# 01-PCIe_40pin.net
KiCad netlist of a schematic drawn in Altium Designer
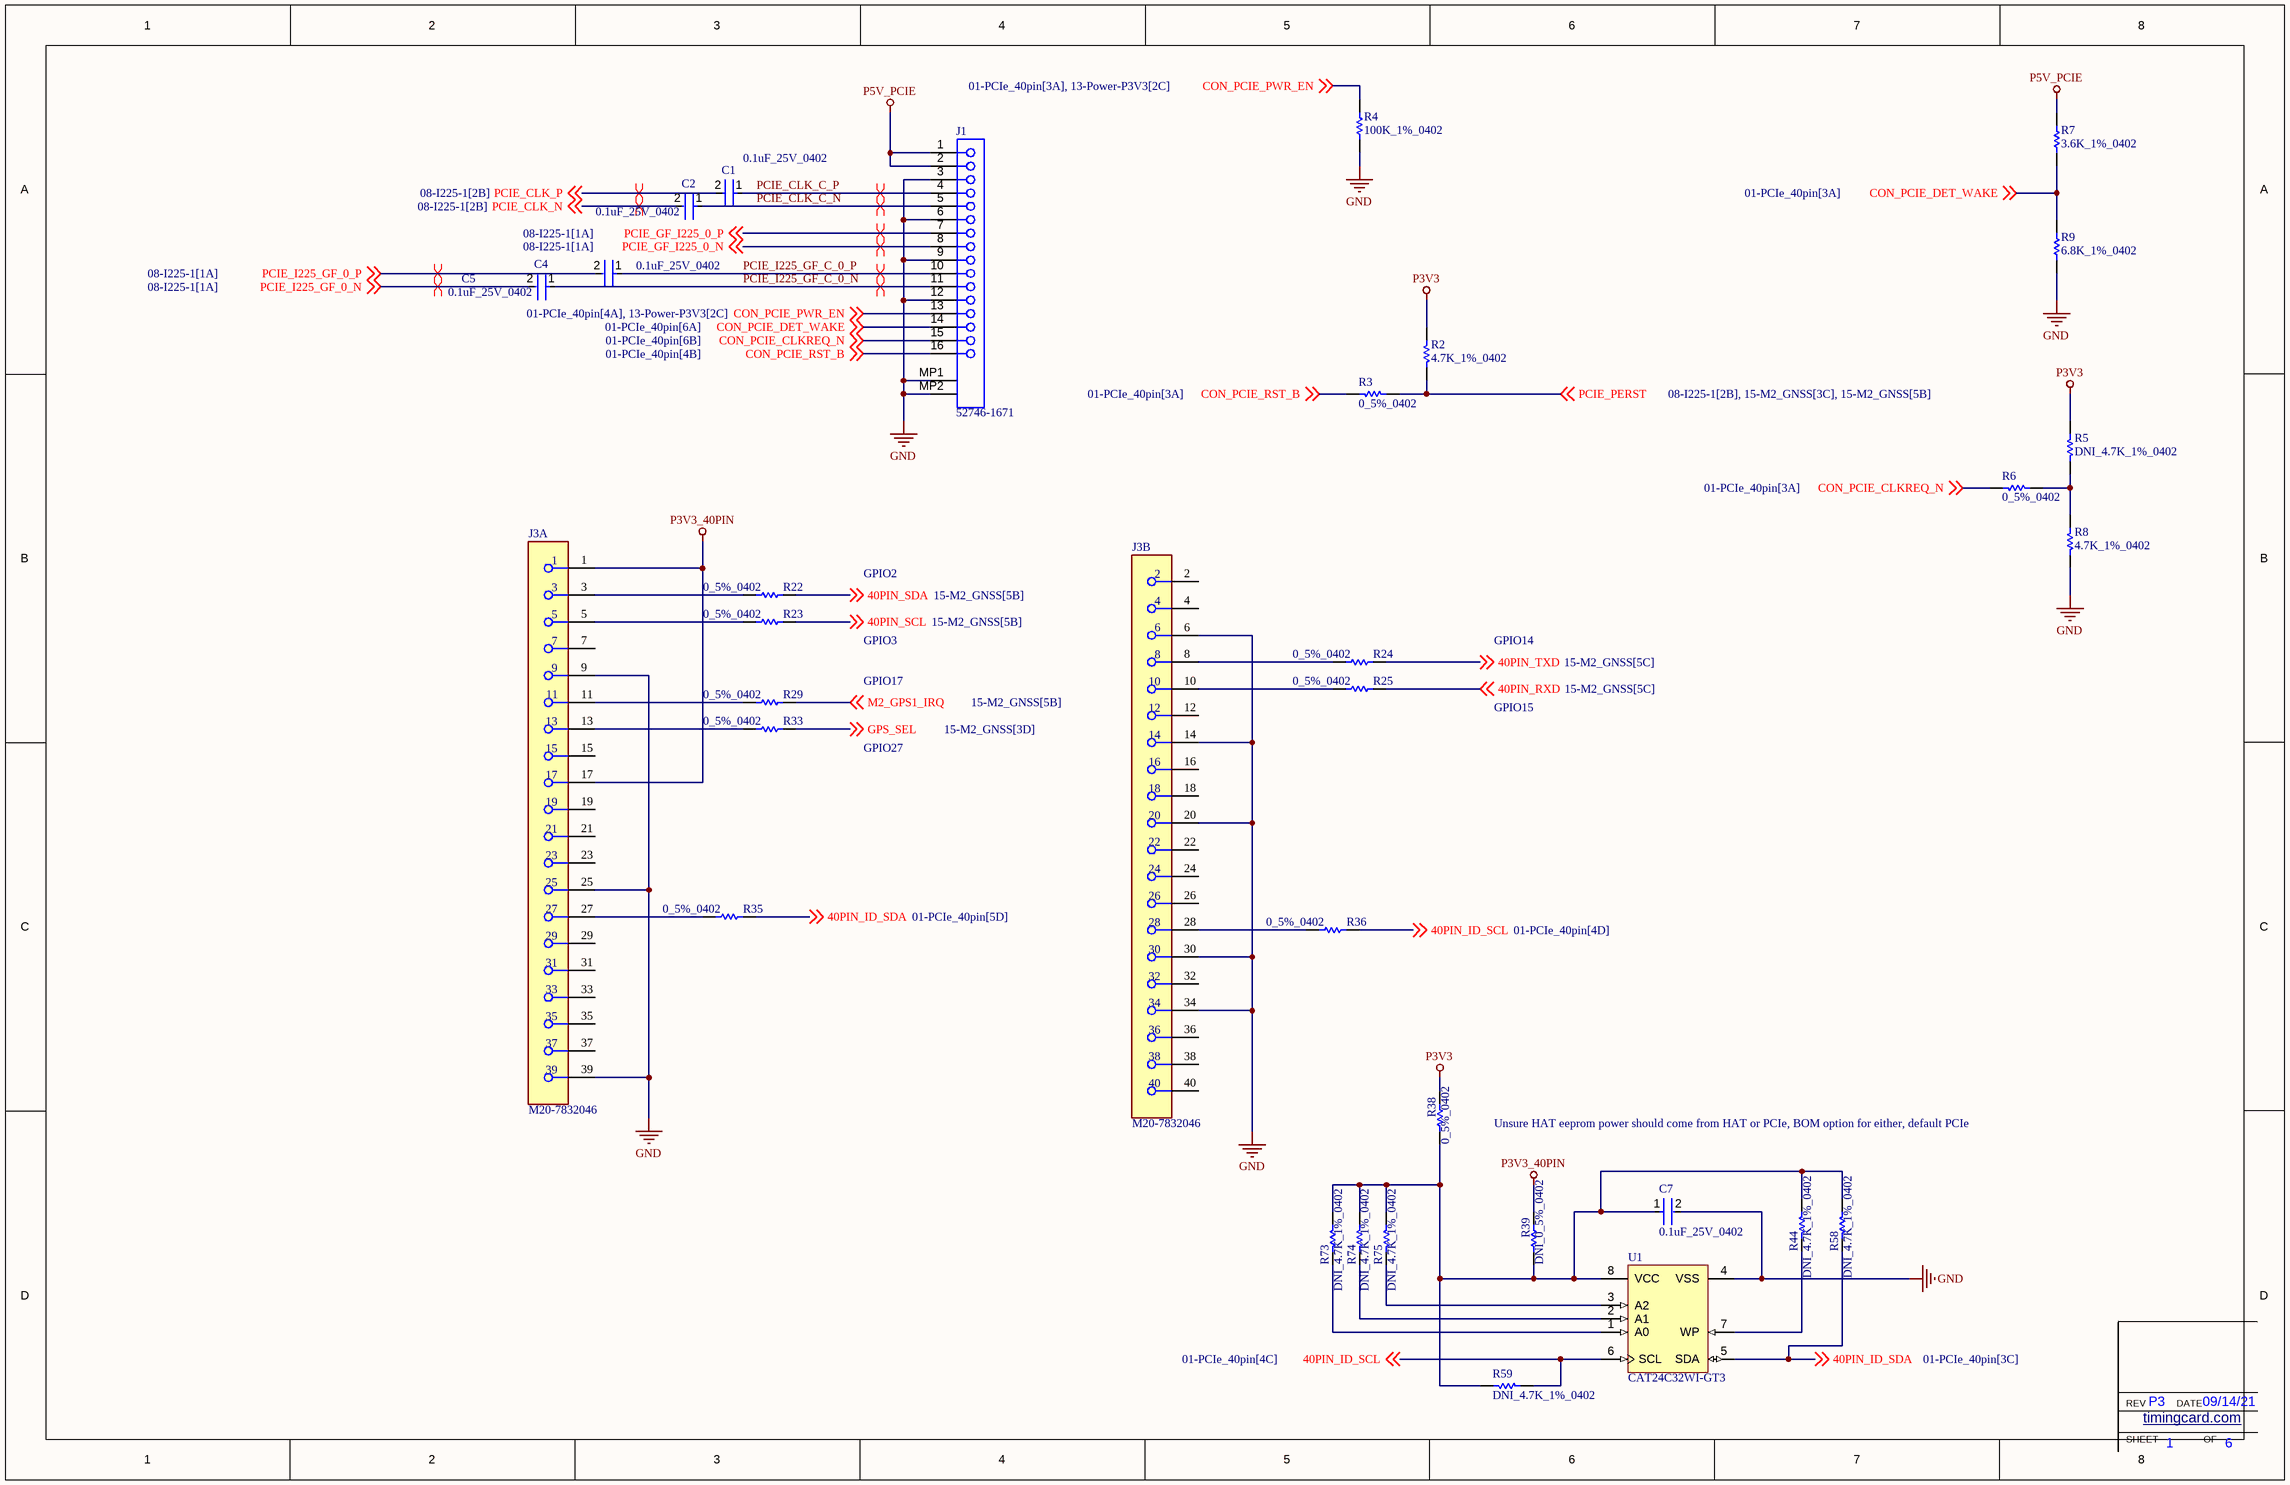
[diagram p0: 01-PCIe_40pin.SchDoc]

(export (version "E")
  (design (tool "Eeschema 10.0.6"))
  (components
    (comp (ref "C1")
      (value "0.1uF_25V_0402")
      (footprint "FP-0402-L_1_0_1-W_0_5_0_1-IPC_C")
      (description "General Purpose Ceramic Capacitor, 0402, 100nF, 10%, X7R, 15%, 25V")
      (fields (field (name "VOLTAGE") "25V") (field (name "TOLERANCE") "10%"))
      (libsource (lib "Altium Content Vault") (part "b4654b650e69147ec39a6b967a45e02"))
    )
    (comp (ref "C2")
      (value "0.1uF_25V_0402")
      (footprint "FP-0402-L_1_0_1-W_0_5_0_1-IPC_C")
      (description "General Purpose Ceramic Capacitor, 0402, 100nF, 10%, X7R, 15%, 25V")
      (fields (field (name "VOLTAGE") "25V") (field (name "TOLERANCE") "10%"))
      (libsource (lib "Altium Content Vault") (part "b4654b650e69147ec39a6b967a45e02"))
    )
    (comp (ref "C4")
      (value "0.1uF_25V_0402")
      (footprint "FP-0402-L_1_0_1-W_0_5_0_1-IPC_C")
      (description "General Purpose Ceramic Capacitor, 0402, 100nF, 10%, X7R, 15%, 25V")
      (fields (field (name "VOLTAGE") "25V") (field (name "TOLERANCE") "10%"))
      (libsource (lib "Altium Content Vault") (part "b4654b650e69147ec39a6b967a45e02"))
    )
    (comp (ref "C5")
      (value "0.1uF_25V_0402")
      (footprint "FP-0402-L_1_0_1-W_0_5_0_1-IPC_C")
      (description "General Purpose Ceramic Capacitor, 0402, 100nF, 10%, X7R, 15%, 25V")
      (fields (field (name "VOLTAGE") "25V") (field (name "TOLERANCE") "10%"))
      (libsource (lib "Altium Content Vault") (part "b4654b650e69147ec39a6b967a45e02"))
    )
    (comp (ref "C7")
      (value "0.1uF_25V_0402")
      (footprint "FP-0402-L_1_0_1-W_0_5_0_1-IPC_C")
      (description "General Purpose Ceramic Capacitor, 0402, 100nF, 10%, X7R, 15%, 25V")
      (fields (field (name "VOLTAGE") "25V") (field (name "TOLERANCE") "10%"))
      (libsource (lib "Altium Content Vault") (part "b4654b650e69147ec39a6b967a45e02"))
    )
    (comp (ref "J1")
      (value "52746-1671")
      (footprint "MOLX-52746-1671")
      (fields (field (name "MANUFACTURER") "Molex"))
      (libsource (lib "Altium Content Vault") (part "MOLX-52746-1671"))
    )
    (comp (ref "J3")
      (value "M20-7832046")
      (footprint "FP-M20-7832046-MFG")
      (description "CONN RCPT 40POS 0.1 TIN PCB")
      (libsource (lib "Altium Content Vault") (part "e49c40d8a4b72700ef4f9e86232dadc"))
    )
    (comp (ref "R2")
      (value "4.7K_1%_0402")
      (footprint "RESC1005X40X25NL10T10")
      (fields (field (name "MANUFACTURER") "Bourns") (field (name "PART NUMBER") "CR0402-FX-4701GLF"))
      (libsource (lib "Altium Content Vault") (part "RES"))
    )
    (comp (ref "R3")
      (value "0_5%_0402")
      (footprint "RESC1005X40X25LL10T10")
      (fields (field (name "MANUFACTURER") "KOA Speer") (field (name "PART NUMBER") "RK73Z1ETTP"))
      (libsource (lib "Altium Content Vault") (part "RES"))
    )
    (comp (ref "R4")
      (value "100K_1%_0402")
      (footprint "RESC1005X40X25ML05T10")
      (fields (field (name "MANUFACTURER") "Yageo") (field (name "PART NUMBER") "RC0402FR-13100KL"))
      (libsource (lib "Altium Content Vault") (part "RES"))
    )
    (comp (ref "R5")
      (value "DNI_4.7K_1%_0402")
      (footprint "RESC1005X40X25NL10T10")
      (fields (field (name "MANUFACTURER") "Bourns") (field (name "PART NUMBER") "CR0402-FX-4701GLF"))
      (libsource (lib "Altium Content Vault") (part "RES"))
    )
    (comp (ref "R6")
      (value "0_5%_0402")
      (footprint "RESC1005X40X25LL10T10")
      (fields (field (name "MANUFACTURER") "KOA Speer") (field (name "PART NUMBER") "RK73Z1ETTP"))
      (libsource (lib "Altium Content Vault") (part "RES"))
    )
    (comp (ref "R7")
      (value "3.6K_1%_0402")
      (footprint "RESC1005X40X25ML05T10")
      (fields (field (name "MANUFACTURER") "Yageo / Phycomp") (field (name "PART NUMBER") "RC0402FR-073K6L"))
      (libsource (lib "Altium Content Vault") (part "RES"))
    )
    (comp (ref "R8")
      (value "4.7K_1%_0402")
      (footprint "RESC1005X40X25NL10T10")
      (fields (field (name "MANUFACTURER") "Bourns") (field (name "PART NUMBER") "CR0402-FX-4701GLF"))
      (libsource (lib "Altium Content Vault") (part "RES"))
    )
    (comp (ref "R9")
      (value "6.8K_1%_0402")
      (footprint "RESC1005X40X25LL10T10")
      (fields (field (name "PART NUMBER") "MC00625W040216K8") (field (name "MANUFACTURER") "Multicomp"))
      (libsource (lib "Altium Content Vault") (part "RES"))
    )
    (comp (ref "R22")
      (value "0_5%_0402")
      (footprint "RESC1005X40X25LL10T10")
      (fields (field (name "MANUFACTURER") "KOA Speer") (field (name "PART NUMBER") "RK73Z1ETTP"))
      (libsource (lib "Altium Content Vault") (part "RES"))
    )
    (comp (ref "R23")
      (value "0_5%_0402")
      (footprint "RESC1005X40X25LL10T10")
      (fields (field (name "MANUFACTURER") "KOA Speer") (field (name "PART NUMBER") "RK73Z1ETTP"))
      (libsource (lib "Altium Content Vault") (part "RES"))
    )
    (comp (ref "R24")
      (value "0_5%_0402")
      (footprint "RESC1005X40X25LL10T10")
      (fields (field (name "MANUFACTURER") "KOA Speer") (field (name "PART NUMBER") "RK73Z1ETTP"))
      (libsource (lib "Altium Content Vault") (part "RES"))
    )
    (comp (ref "R25")
      (value "0_5%_0402")
      (footprint "RESC1005X40X25LL10T10")
      (fields (field (name "MANUFACTURER") "KOA Speer") (field (name "PART NUMBER") "RK73Z1ETTP"))
      (libsource (lib "Altium Content Vault") (part "RES"))
    )
    (comp (ref "R29")
      (value "0_5%_0402")
      (footprint "RESC1005X40X25LL10T10")
      (fields (field (name "MANUFACTURER") "KOA Speer") (field (name "PART NUMBER") "RK73Z1ETTP"))
      (libsource (lib "Altium Content Vault") (part "RES"))
    )
    (comp (ref "R33")
      (value "0_5%_0402")
      (footprint "RESC1005X40X25LL10T10")
      (fields (field (name "MANUFACTURER") "KOA Speer") (field (name "PART NUMBER") "RK73Z1ETTP"))
      (libsource (lib "Altium Content Vault") (part "RES"))
    )
    (comp (ref "R35")
      (value "0_5%_0402")
      (footprint "RESC1005X40X25LL10T10")
      (fields (field (name "MANUFACTURER") "KOA Speer") (field (name "PART NUMBER") "RK73Z1ETTP"))
      (libsource (lib "Altium Content Vault") (part "RES"))
    )
    (comp (ref "R36")
      (value "0_5%_0402")
      (footprint "RESC1005X40X25LL10T10")
      (fields (field (name "MANUFACTURER") "KOA Speer") (field (name "PART NUMBER") "RK73Z1ETTP"))
      (libsource (lib "Altium Content Vault") (part "RES"))
    )
    (comp (ref "R38")
      (value "0_5%_0402")
      (footprint "RESC1005X40X25LL10T10")
      (fields (field (name "MANUFACTURER") "KOA Speer") (field (name "PART NUMBER") "RK73Z1ETTP"))
      (libsource (lib "Altium Content Vault") (part "RES"))
    )
    (comp (ref "R39")
      (value "DNI_0_5%_0402")
      (footprint "RESC1005X40X25LL10T10")
      (fields (field (name "MANUFACTURER") "KOA Speer") (field (name "PART NUMBER") "RK73Z1ETTP"))
      (libsource (lib "Altium Content Vault") (part "RES"))
    )
    (comp (ref "R44")
      (value "DNI_4.7K_1%_0402")
      (footprint "RESC1005X40X25NL10T10")
      (fields (field (name "MANUFACTURER") "Bourns") (field (name "PART NUMBER") "CR0402-FX-4701GLF"))
      (libsource (lib "Altium Content Vault") (part "RES"))
    )
    (comp (ref "R58")
      (value "DNI_4.7K_1%_0402")
      (footprint "RESC1005X40X25NL10T10")
      (fields (field (name "MANUFACTURER") "Bourns") (field (name "PART NUMBER") "CR0402-FX-4701GLF"))
      (libsource (lib "Altium Content Vault") (part "RES"))
    )
    (comp (ref "R59")
      (value "DNI_4.7K_1%_0402")
      (footprint "RESC1005X40X25NL10T10")
      (fields (field (name "MANUFACTURER") "Bourns") (field (name "PART NUMBER") "CR0402-FX-4701GLF"))
      (libsource (lib "Altium Content Vault") (part "RES"))
    )
    (comp (ref "R73")
      (value "DNI_4.7K_1%_0402")
      (footprint "RESC1005X40X25NL10T10")
      (fields (field (name "MANUFACTURER") "Bourns") (field (name "PART NUMBER") "CR0402-FX-4701GLF"))
      (libsource (lib "Altium Content Vault") (part "RES"))
    )
    (comp (ref "R74")
      (value "DNI_4.7K_1%_0402")
      (footprint "RESC1005X40X25NL10T10")
      (fields (field (name "MANUFACTURER") "Bourns") (field (name "PART NUMBER") "CR0402-FX-4701GLF"))
      (libsource (lib "Altium Content Vault") (part "RES"))
    )
    (comp (ref "R75")
      (value "DNI_4.7K_1%_0402")
      (footprint "RESC1005X40X25NL10T10")
      (fields (field (name "MANUFACTURER") "Bourns") (field (name "PART NUMBER") "CR0402-FX-4701GLF"))
      (libsource (lib "Altium Content Vault") (part "RES"))
    )
    (comp (ref "U1")
      (value "CAT24C32WI-GT3")
      (footprint "ONSC-SOIC-8-751BD-01_M")
      (libsource (lib "Altium Content Vault") (part "ONSC-CAT24C32-SOIC-8"))
    )
  )
  (nets
    (net (code "1") (name "/PCIE_CLK_C_N") (class "Default")
      (node (ref "C2") (pin "1") (pinfunction "1_1") (pintype "passive"))
      (node (ref "J1") (pin "5") (pinfunction "5_5") (pintype "passive"))
    )
    (net (code "2") (name "/PCIE_CLK_C_P") (class "Default")
      (node (ref "C1") (pin "1") (pinfunction "1_1") (pintype "passive"))
      (node (ref "J1") (pin "4") (pinfunction "4_4") (pintype "passive"))
    )
    (net (code "3") (name "/PCIE_I225_GF_C_0_N") (class "Default")
      (node (ref "C4") (pin "1") (pinfunction "1_1") (pintype "passive"))
      (node (ref "J1") (pin "11") (pinfunction "11_11") (pintype "passive"))
    )
    (net (code "4") (name "/PCIE_I225_GF_C_0_P") (class "Default")
      (node (ref "C5") (pin "1") (pinfunction "1_1") (pintype "passive"))
      (node (ref "J1") (pin "10") (pinfunction "10_10") (pintype "passive"))
    )
    (net (code "5") (name "40PIN_ID_SCL") (class "Default")
      (node (ref "R36") (pin "2") (pinfunction "2_2") (pintype "passive"))
      (node (ref "R59") (pin "1") (pinfunction "1_1") (pintype "passive"))
      (node (ref "U1") (pin "6") (pinfunction "SCL_6") (pintype "input"))
    )
    (net (code "6") (name "40PIN_ID_SDA") (class "Default")
      (node (ref "R35") (pin "2") (pinfunction "2_2") (pintype "passive"))
      (node (ref "R58") (pin "1") (pinfunction "1_1") (pintype "passive"))
      (node (ref "U1") (pin "5") (pinfunction "SDA_5") (pintype "bidirectional"))
    )
    (net (code "7") (name "40PIN_RXD") (class "Default")
      (node (ref "R25") (pin "2") (pinfunction "2_2") (pintype "passive"))
    )
    (net (code "8") (name "40PIN_SCL") (class "Default")
      (node (ref "R23") (pin "2") (pinfunction "2_2") (pintype "passive"))
    )
    (net (code "9") (name "40PIN_SDA") (class "Default")
      (node (ref "R22") (pin "2") (pinfunction "2_2") (pintype "passive"))
    )
    (net (code "10") (name "40PIN_TXD") (class "Default")
      (node (ref "R24") (pin "2") (pinfunction "2_2") (pintype "passive"))
    )
    (net (code "11") (name "CON_PCIE_CLKREQ_N") (class "Default")
      (node (ref "J1") (pin "15") (pinfunction "15_15") (pintype "passive"))
      (node (ref "R6") (pin "2") (pinfunction "2_2") (pintype "passive"))
    )
    (net (code "12") (name "CON_PCIE_DET_WAKE") (class "Default")
      (node (ref "J1") (pin "14") (pinfunction "14_14") (pintype "passive"))
      (node (ref "R7") (pin "1") (pinfunction "1_1") (pintype "passive"))
      (node (ref "R9") (pin "2") (pinfunction "2_2") (pintype "passive"))
    )
    (net (code "13") (name "CON_PCIE_PWR_EN") (class "Default")
      (node (ref "J1") (pin "13") (pinfunction "13_13") (pintype "passive"))
      (node (ref "R4") (pin "2") (pinfunction "2_2") (pintype "passive"))
    )
    (net (code "14") (name "CON_PCIE_RST_B") (class "Default")
      (node (ref "J1") (pin "16") (pinfunction "16_16") (pintype "passive"))
      (node (ref "R3") (pin "2") (pinfunction "2_2") (pintype "passive"))
    )
    (net (code "15") (name "GND") (class "Default")
      (node (ref "C7") (pin "2") (pinfunction "2_2") (pintype "passive"))
      (node (ref "J1") (pin "12") (pinfunction "12_12") (pintype "passive"))
      (node (ref "J1") (pin "3") (pinfunction "3_3") (pintype "passive"))
      (node (ref "J1") (pin "6") (pinfunction "6_6") (pintype "passive"))
      (node (ref "J1") (pin "9") (pinfunction "9_9") (pintype "passive"))
      (node (ref "J1") (pin "MP1") (pinfunction "MP1_MP1") (pintype "passive"))
      (node (ref "J1") (pin "MP2") (pinfunction "MP2_MP2") (pintype "passive"))
      (node (ref "J3") (pin "14") (pinfunction "14_14") (pintype "passive"))
      (node (ref "J3") (pin "20") (pinfunction "20_20") (pintype "passive"))
      (node (ref "J3") (pin "25") (pinfunction "25_25") (pintype "passive"))
      (node (ref "J3") (pin "30") (pinfunction "30_30") (pintype "passive"))
      (node (ref "J3") (pin "34") (pinfunction "34_34") (pintype "passive"))
      (node (ref "J3") (pin "39") (pinfunction "39_39") (pintype "passive"))
      (node (ref "J3") (pin "6") (pinfunction "6_6") (pintype "passive"))
      (node (ref "J3") (pin "9") (pinfunction "9_9") (pintype "passive"))
      (node (ref "R4") (pin "1") (pinfunction "1_1") (pintype "passive"))
      (node (ref "R8") (pin "1") (pinfunction "1_1") (pintype "passive"))
      (node (ref "R9") (pin "1") (pinfunction "1_1") (pintype "passive"))
      (node (ref "U1") (pin "4") (pinfunction "VSS_4") (pintype "power_in"))
    )
    (net (code "16") (name "GPS_SEL") (class "Default")
      (node (ref "R33") (pin "2") (pinfunction "2_2") (pintype "passive"))
    )
    (net (code "17") (name "M2_GPS1_IRQ") (class "Default")
      (node (ref "R29") (pin "2") (pinfunction "2_2") (pintype "passive"))
    )
    (net (code "18") (name "Net-(J3-Pad3)") (class "Default")
      (node (ref "J3") (pin "3") (pinfunction "3_3") (pintype "passive"))
      (node (ref "R22") (pin "1") (pinfunction "1_1") (pintype "passive"))
    )
    (net (code "19") (name "Net-(J3-Pad5)") (class "Default")
      (node (ref "J3") (pin "5") (pinfunction "5_5") (pintype "passive"))
      (node (ref "R23") (pin "1") (pinfunction "1_1") (pintype "passive"))
    )
    (net (code "20") (name "Net-(J3-Pad8)") (class "Default")
      (node (ref "J3") (pin "8") (pinfunction "8_8") (pintype "passive"))
      (node (ref "R24") (pin "1") (pinfunction "1_1") (pintype "passive"))
    )
    (net (code "21") (name "Net-(J3-Pad10)") (class "Default")
      (node (ref "J3") (pin "10") (pinfunction "10_10") (pintype "passive"))
      (node (ref "R25") (pin "1") (pinfunction "1_1") (pintype "passive"))
    )
    (net (code "22") (name "Net-(J3-Pad11)") (class "Default")
      (node (ref "J3") (pin "11") (pinfunction "11_11") (pintype "passive"))
      (node (ref "R29") (pin "1") (pinfunction "1_1") (pintype "passive"))
    )
    (net (code "23") (name "Net-(J3-Pad13)") (class "Default")
      (node (ref "J3") (pin "13") (pinfunction "13_13") (pintype "passive"))
      (node (ref "R33") (pin "1") (pinfunction "1_1") (pintype "passive"))
    )
    (net (code "24") (name "Net-(J3-Pad27)") (class "Default")
      (node (ref "J3") (pin "27") (pinfunction "27_27") (pintype "passive"))
      (node (ref "R35") (pin "1") (pinfunction "1_1") (pintype "passive"))
    )
    (net (code "25") (name "Net-(J3-Pad28)") (class "Default")
      (node (ref "J3") (pin "28") (pinfunction "28_28") (pintype "passive"))
      (node (ref "R36") (pin "1") (pinfunction "1_1") (pintype "passive"))
    )
    (net (code "26") (name "Net-(R5-Pad1)") (class "Default")
      (node (ref "R5") (pin "1") (pinfunction "1_1") (pintype "passive"))
      (node (ref "R6") (pin "1") (pinfunction "1_1") (pintype "passive"))
      (node (ref "R8") (pin "2") (pinfunction "2_2") (pintype "passive"))
    )
    (net (code "27") (name "Net-(U1-A0)") (class "Default")
      (node (ref "R73") (pin "1") (pinfunction "1_1") (pintype "passive"))
      (node (ref "U1") (pin "1") (pinfunction "A0_1") (pintype "input"))
    )
    (net (code "28") (name "Net-(U1-A1)") (class "Default")
      (node (ref "R74") (pin "1") (pinfunction "1_1") (pintype "passive"))
      (node (ref "U1") (pin "2") (pinfunction "A1_2") (pintype "input"))
    )
    (net (code "29") (name "Net-(U1-A2)") (class "Default")
      (node (ref "R75") (pin "1") (pinfunction "1_1") (pintype "passive"))
      (node (ref "U1") (pin "3") (pinfunction "A2_3") (pintype "input"))
    )
    (net (code "30") (name "Net-(U1-VCC)") (class "Default")
      (node (ref "C7") (pin "1") (pinfunction "1_1") (pintype "passive"))
      (node (ref "R38") (pin "1") (pinfunction "1_1") (pintype "passive"))
      (node (ref "R39") (pin "1") (pinfunction "1_1") (pintype "passive"))
      (node (ref "R44") (pin "2") (pinfunction "2_2") (pintype "passive"))
      (node (ref "R58") (pin "2") (pinfunction "2_2") (pintype "passive"))
      (node (ref "R59") (pin "2") (pinfunction "2_2") (pintype "passive"))
      (node (ref "R73") (pin "2") (pinfunction "2_2") (pintype "passive"))
      (node (ref "R74") (pin "2") (pinfunction "2_2") (pintype "passive"))
      (node (ref "R75") (pin "2") (pinfunction "2_2") (pintype "passive"))
      (node (ref "U1") (pin "8") (pinfunction "VCC_8") (pintype "power_in"))
    )
    (net (code "31") (name "Net-(U1-WP)") (class "Default")
      (node (ref "R44") (pin "1") (pinfunction "1_1") (pintype "passive"))
      (node (ref "U1") (pin "7") (pinfunction "WP_7") (pintype "input"))
    )
    (net (code "32") (name "P3V3") (class "Default")
      (node (ref "R2") (pin "2") (pinfunction "2_2") (pintype "passive"))
      (node (ref "R38") (pin "2") (pinfunction "2_2") (pintype "passive"))
      (node (ref "R5") (pin "2") (pinfunction "2_2") (pintype "passive"))
    )
    (net (code "33") (name "P3V3_40PIN") (class "Default")
      (node (ref "J3") (pin "1") (pinfunction "1_1") (pintype "passive"))
      (node (ref "J3") (pin "17") (pinfunction "17_17") (pintype "passive"))
      (node (ref "R39") (pin "2") (pinfunction "2_2") (pintype "passive"))
    )
    (net (code "34") (name "P5V_PCIE") (class "Default")
      (node (ref "J1") (pin "1") (pinfunction "1_1") (pintype "passive"))
      (node (ref "J1") (pin "2") (pinfunction "2_2") (pintype "passive"))
      (node (ref "R7") (pin "2") (pinfunction "2_2") (pintype "passive"))
    )
    (net (code "35") (name "PCIE_CLK_N") (class "Default")
      (node (ref "C2") (pin "2") (pinfunction "2_2") (pintype "passive"))
    )
    (net (code "36") (name "PCIE_CLK_P") (class "Default")
      (node (ref "C1") (pin "2") (pinfunction "2_2") (pintype "passive"))
    )
    (net (code "37") (name "PCIE_GF_I225_0_N") (class "Default")
      (node (ref "J1") (pin "8") (pinfunction "8_8") (pintype "passive"))
    )
    (net (code "38") (name "PCIE_GF_I225_0_P") (class "Default")
      (node (ref "J1") (pin "7") (pinfunction "7_7") (pintype "passive"))
    )
    (net (code "39") (name "PCIE_I225_GF_0_N") (class "Default")
      (node (ref "C4") (pin "2") (pinfunction "2_2") (pintype "passive"))
    )
    (net (code "40") (name "PCIE_I225_GF_0_P") (class "Default")
      (node (ref "C5") (pin "2") (pinfunction "2_2") (pintype "passive"))
    )
    (net (code "41") (name "PCIE_PERST") (class "Default")
      (node (ref "R2") (pin "1") (pinfunction "1_1") (pintype "passive"))
      (node (ref "R3") (pin "1") (pinfunction "1_1") (pintype "passive"))
    )
    (net (code "42") (name "unconnected-(J3-Pad2)") (class "Default")
      (node (ref "J3") (pin "2") (pinfunction "2_2") (pintype "passive"))
    )
    (net (code "43") (name "unconnected-(J3-Pad4)") (class "Default")
      (node (ref "J3") (pin "4") (pinfunction "4_4") (pintype "passive"))
    )
    (net (code "44") (name "unconnected-(J3-Pad7)") (class "Default")
      (node (ref "J3") (pin "7") (pinfunction "7_7") (pintype "passive"))
    )
    (net (code "45") (name "unconnected-(J3-Pad12)") (class "Default")
      (node (ref "J3") (pin "12") (pinfunction "12_12") (pintype "passive"))
    )
    (net (code "46") (name "unconnected-(J3-Pad15)") (class "Default")
      (node (ref "J3") (pin "15") (pinfunction "15_15") (pintype "passive"))
    )
    (net (code "47") (name "unconnected-(J3-Pad16)") (class "Default")
      (node (ref "J3") (pin "16") (pinfunction "16_16") (pintype "passive"))
    )
    (net (code "48") (name "unconnected-(J3-Pad18)") (class "Default")
      (node (ref "J3") (pin "18") (pinfunction "18_18") (pintype "passive"))
    )
    (net (code "49") (name "unconnected-(J3-Pad19)") (class "Default")
      (node (ref "J3") (pin "19") (pinfunction "19_19") (pintype "passive"))
    )
    (net (code "50") (name "unconnected-(J3-Pad21)") (class "Default")
      (node (ref "J3") (pin "21") (pinfunction "21_21") (pintype "passive"))
    )
    (net (code "51") (name "unconnected-(J3-Pad22)") (class "Default")
      (node (ref "J3") (pin "22") (pinfunction "22_22") (pintype "passive"))
    )
    (net (code "52") (name "unconnected-(J3-Pad23)") (class "Default")
      (node (ref "J3") (pin "23") (pinfunction "23_23") (pintype "passive"))
    )
    (net (code "53") (name "unconnected-(J3-Pad24)") (class "Default")
      (node (ref "J3") (pin "24") (pinfunction "24_24") (pintype "passive"))
    )
    (net (code "54") (name "unconnected-(J3-Pad26)") (class "Default")
      (node (ref "J3") (pin "26") (pinfunction "26_26") (pintype "passive"))
    )
    (net (code "55") (name "unconnected-(J3-Pad29)") (class "Default")
      (node (ref "J3") (pin "29") (pinfunction "29_29") (pintype "passive"))
    )
    (net (code "56") (name "unconnected-(J3-Pad31)") (class "Default")
      (node (ref "J3") (pin "31") (pinfunction "31_31") (pintype "passive"))
    )
    (net (code "57") (name "unconnected-(J3-Pad32)") (class "Default")
      (node (ref "J3") (pin "32") (pinfunction "32_32") (pintype "passive"))
    )
    (net (code "58") (name "unconnected-(J3-Pad33)") (class "Default")
      (node (ref "J3") (pin "33") (pinfunction "33_33") (pintype "passive"))
    )
    (net (code "59") (name "unconnected-(J3-Pad35)") (class "Default")
      (node (ref "J3") (pin "35") (pinfunction "35_35") (pintype "passive"))
    )
    (net (code "60") (name "unconnected-(J3-Pad36)") (class "Default")
      (node (ref "J3") (pin "36") (pinfunction "36_36") (pintype "passive"))
    )
    (net (code "61") (name "unconnected-(J3-Pad37)") (class "Default")
      (node (ref "J3") (pin "37") (pinfunction "37_37") (pintype "passive"))
    )
    (net (code "62") (name "unconnected-(J3-Pad38)") (class "Default")
      (node (ref "J3") (pin "38") (pinfunction "38_38") (pintype "passive"))
    )
    (net (code "63") (name "unconnected-(J3-Pad40)") (class "Default")
      (node (ref "J3") (pin "40") (pinfunction "40_40") (pintype "passive"))
    )
  )
)
